# EstMeteoSCH.net
KiCad netlist of a schematic drawn in Altium Designer
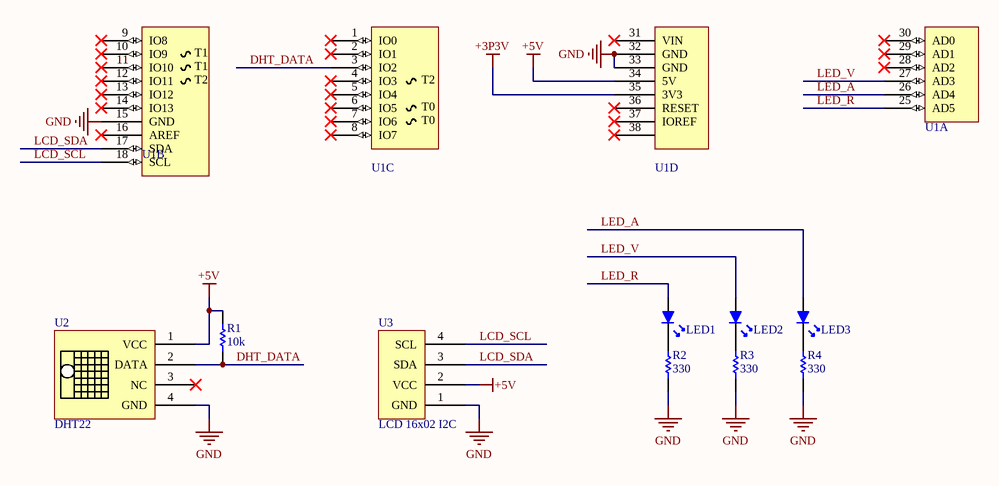
[diagram p0: EstMeteoSCH.SchDoc]

(export (version "E")
  (design (tool "Eeschema 10.0.6"))
  (components
    (comp (ref "LED1")
      (value "LED")
      (footprint "LED 1206")
      (fields (field (name ".CREATOR") "SR"))
      (libsource (lib "EstacionMetereologicaSCH") (part "LED"))
    )
    (comp (ref "LED2")
      (value "LED")
      (footprint "LED 1206")
      (fields (field (name ".CREATOR") "SR"))
      (libsource (lib "EstacionMetereologicaSCH") (part "LED"))
    )
    (comp (ref "LED3")
      (value "LED")
      (footprint "LED 1206")
      (fields (field (name ".CREATOR") "SR"))
      (libsource (lib "EstacionMetereologicaSCH") (part "LED"))
    )
    (comp (ref "R1")
      (value "10k")
      (footprint "R 1206")
      (description "Resistencia")
      (fields (field (name ".CREATOR") "SR"))
      (libsource (lib "EstacionMetereologicaSCH") (part "R"))
    )
    (comp (ref "R2")
      (value "330")
      (footprint "R 1206")
      (description "Resistencia")
      (fields (field (name ".CREATOR") "SR"))
      (libsource (lib "EstacionMetereologicaSCH") (part "R"))
    )
    (comp (ref "R3")
      (value "330")
      (footprint "R 1206")
      (description "Resistencia")
      (fields (field (name ".CREATOR") "SR"))
      (libsource (lib "EstacionMetereologicaSCH") (part "R"))
    )
    (comp (ref "R4")
      (value "330")
      (footprint "R 1206")
      (description "Resistencia")
      (fields (field (name ".CREATOR") "SR"))
      (libsource (lib "EstacionMetereologicaSCH") (part "R"))
    )
    (comp (ref "U1")
      (value "ARDUINO UNO SIN MISOMOSI")
      (footprint "ARDUINO_SHIELD_SIN_MALE")
      (libsource (lib "EstacionMetereologicaSCH") (part "ARDUINO UNO SIN MISOMOSI"))
    )
    (comp (ref "U2")
      (value "DHT22")
      (footprint "DHT22")
      (description "SENSOR TEMP/HUMIDTY AM2302 DHT22")
      (fields
        (field (name "MANUFACTURER") "Adafruit Industries LLC")
        (field (name "MANUFACTURER PART NUMBER") "393")
      )
      (libsource (lib "EstacionMetereologicaSCH") (part "393"))
    )
    (comp (ref "U3")
      (value "LCD 16x02 I2C")
      (footprint "LCD I2C")
      (description "LCD MODULE 16X2 CHARACTER")
      (fields
        (field (name "MANUFACTURER") "Lumex Opto/Components Inc.")
        (field (name "MANUFACTURER PART NUMBER") "LCM-S01602DTR/A")
      )
      (libsource (lib "EstacionMetereologicaSCH") (part "LCM-S01602DTR/A"))
    )
  )
  (nets
    (net (code "1") (name "+3P3V") (class "Default")
      (node (ref "U1") (pin "35") (pinfunction "3V3_35") (pintype "power_in"))
    )
    (net (code "2") (name "+5V") (class "Default")
      (node (ref "R1") (pin "2") (pinfunction "2_2") (pintype "passive"))
      (node (ref "U1") (pin "34") (pinfunction "5V_34") (pintype "power_in"))
      (node (ref "U2") (pin "1") (pinfunction "VCC_1") (pintype "passive"))
      (node (ref "U3") (pin "2") (pinfunction "VCC_2") (pintype "passive"))
    )
    (net (code "3") (name "/DHT_DATA") (class "Default")
      (node (ref "R1") (pin "1") (pinfunction "1_1") (pintype "passive"))
      (node (ref "U1") (pin "3") (pinfunction "IO2_3") (pintype "bidirectional"))
      (node (ref "U2") (pin "2") (pinfunction "DATA_2") (pintype "passive"))
    )
    (net (code "4") (name "/LCD_SCL") (class "Default")
      (node (ref "U1") (pin "18") (pinfunction "SCL_18") (pintype "bidirectional"))
      (node (ref "U3") (pin "4") (pinfunction "SCL_4") (pintype "passive"))
    )
    (net (code "5") (name "/LCD_SDA") (class "Default")
      (node (ref "U1") (pin "17") (pinfunction "SDA_17") (pintype "bidirectional"))
      (node (ref "U3") (pin "3") (pinfunction "SDA_3") (pintype "passive"))
    )
    (net (code "6") (name "/LED_A") (class "Default")
      (node (ref "LED3") (pin "1") (pinfunction "A_1") (pintype "passive"))
      (node (ref "U1") (pin "26") (pinfunction "AD4_26") (pintype "bidirectional"))
    )
    (net (code "7") (name "/LED_R") (class "Default")
      (node (ref "LED1") (pin "1") (pinfunction "A_1") (pintype "passive"))
      (node (ref "U1") (pin "25") (pinfunction "AD5_25") (pintype "bidirectional"))
    )
    (net (code "8") (name "/LED_V") (class "Default")
      (node (ref "LED2") (pin "1") (pinfunction "A_1") (pintype "passive"))
      (node (ref "U1") (pin "27") (pinfunction "AD3_27") (pintype "bidirectional"))
    )
    (net (code "9") (name "GND") (class "Default")
      (node (ref "R2") (pin "1") (pinfunction "1_1") (pintype "passive"))
      (node (ref "R3") (pin "1") (pinfunction "1_1") (pintype "passive"))
      (node (ref "R4") (pin "1") (pinfunction "1_1") (pintype "passive"))
      (node (ref "U1") (pin "15") (pinfunction "GND_15") (pintype "power_in"))
      (node (ref "U1") (pin "32") (pinfunction "GND_32") (pintype "power_in"))
      (node (ref "U1") (pin "33") (pinfunction "GND_33") (pintype "power_in"))
      (node (ref "U2") (pin "4") (pinfunction "GND_4") (pintype "passive"))
      (node (ref "U3") (pin "1") (pinfunction "GND_1") (pintype "passive"))
    )
    (net (code "10") (name "Net-(LED1-K)") (class "Default")
      (node (ref "LED1") (pin "2") (pinfunction "K_2") (pintype "passive"))
      (node (ref "R2") (pin "2") (pinfunction "2_2") (pintype "passive"))
    )
    (net (code "11") (name "Net-(LED2-K)") (class "Default")
      (node (ref "LED2") (pin "2") (pinfunction "K_2") (pintype "passive"))
      (node (ref "R3") (pin "2") (pinfunction "2_2") (pintype "passive"))
    )
    (net (code "12") (name "Net-(LED3-K)") (class "Default")
      (node (ref "LED3") (pin "2") (pinfunction "K_2") (pintype "passive"))
      (node (ref "R4") (pin "2") (pinfunction "2_2") (pintype "passive"))
    )
    (net (code "13") (name "unconnected-(U1-Pad38)") (class "Default")
      (node (ref "U1") (pin "38") (pintype "passive+no_connect"))
    )
    (net (code "14") (name "unconnected-(U1A-AD0-Pad30)") (class "Default")
      (node (ref "U1") (pin "30") (pinfunction "AD0_30") (pintype "bidirectional+no_connect"))
    )
    (net (code "15") (name "unconnected-(U1A-AD1-Pad29)") (class "Default")
      (node (ref "U1") (pin "29") (pinfunction "AD1_29") (pintype "bidirectional+no_connect"))
    )
    (net (code "16") (name "unconnected-(U1A-AD2-Pad28)") (class "Default")
      (node (ref "U1") (pin "28") (pinfunction "AD2_28") (pintype "bidirectional+no_connect"))
    )
    (net (code "17") (name "unconnected-(U1B-AREF-Pad16)") (class "Default")
      (node (ref "U1") (pin "16") (pinfunction "AREF_16") (pintype "passive+no_connect"))
    )
    (net (code "18") (name "unconnected-(U1B-IO8-Pad9)") (class "Default")
      (node (ref "U1") (pin "9") (pinfunction "IO8_9") (pintype "bidirectional+no_connect"))
    )
    (net (code "19") (name "unconnected-(U1B-IO9-Pad10)") (class "Default")
      (node (ref "U1") (pin "10") (pinfunction "IO9_10") (pintype "bidirectional+no_connect"))
    )
    (net (code "20") (name "unconnected-(U1B-IO10-Pad11)") (class "Default")
      (node (ref "U1") (pin "11") (pinfunction "IO10_11") (pintype "bidirectional+no_connect"))
    )
    (net (code "21") (name "unconnected-(U1B-IO11-Pad12)") (class "Default")
      (node (ref "U1") (pin "12") (pinfunction "IO11_12") (pintype "bidirectional+no_connect"))
    )
    (net (code "22") (name "unconnected-(U1B-IO12-Pad13)") (class "Default")
      (node (ref "U1") (pin "13") (pinfunction "IO12_13") (pintype "bidirectional+no_connect"))
    )
    (net (code "23") (name "unconnected-(U1B-IO13-Pad14)") (class "Default")
      (node (ref "U1") (pin "14") (pinfunction "IO13_14") (pintype "bidirectional+no_connect"))
    )
    (net (code "24") (name "unconnected-(U1C-IO0-Pad1)") (class "Default")
      (node (ref "U1") (pin "1") (pinfunction "IO0_1") (pintype "bidirectional+no_connect"))
    )
    (net (code "25") (name "unconnected-(U1C-IO1-Pad2)") (class "Default")
      (node (ref "U1") (pin "2") (pinfunction "IO1_2") (pintype "bidirectional+no_connect"))
    )
    (net (code "26") (name "unconnected-(U1C-IO3-Pad4)") (class "Default")
      (node (ref "U1") (pin "4") (pinfunction "IO3_4") (pintype "bidirectional+no_connect"))
    )
    (net (code "27") (name "unconnected-(U1C-IO4-Pad5)") (class "Default")
      (node (ref "U1") (pin "5") (pinfunction "IO4_5") (pintype "bidirectional+no_connect"))
    )
    (net (code "28") (name "unconnected-(U1C-IO5-Pad6)") (class "Default")
      (node (ref "U1") (pin "6") (pinfunction "IO5_6") (pintype "bidirectional+no_connect"))
    )
    (net (code "29") (name "unconnected-(U1C-IO6-Pad7)") (class "Default")
      (node (ref "U1") (pin "7") (pinfunction "IO6_7") (pintype "bidirectional+no_connect"))
    )
    (net (code "30") (name "unconnected-(U1C-IO7-Pad8)") (class "Default")
      (node (ref "U1") (pin "8") (pinfunction "IO7_8") (pintype "bidirectional+no_connect"))
    )
    (net (code "31") (name "unconnected-(U1D-IOREF-Pad37)") (class "Default")
      (node (ref "U1") (pin "37") (pinfunction "IOREF_37") (pintype "power_in+no_connect"))
    )
    (net (code "32") (name "unconnected-(U1D-RESET-Pad36)") (class "Default")
      (node (ref "U1") (pin "36") (pinfunction "RESET_36") (pintype "passive+no_connect"))
    )
    (net (code "33") (name "unconnected-(U1D-VIN-Pad31)") (class "Default")
      (node (ref "U1") (pin "31") (pinfunction "VIN_31") (pintype "power_in+no_connect"))
    )
    (net (code "34") (name "unconnected-(U2-NC-Pad3)") (class "Default")
      (node (ref "U2") (pin "3") (pinfunction "NC_3") (pintype "passive+no_connect"))
    )
  )
)
